# rad_detector_v500_PERIPHERAL.net
KiCad netlist of a schematic drawn in Altium Designer
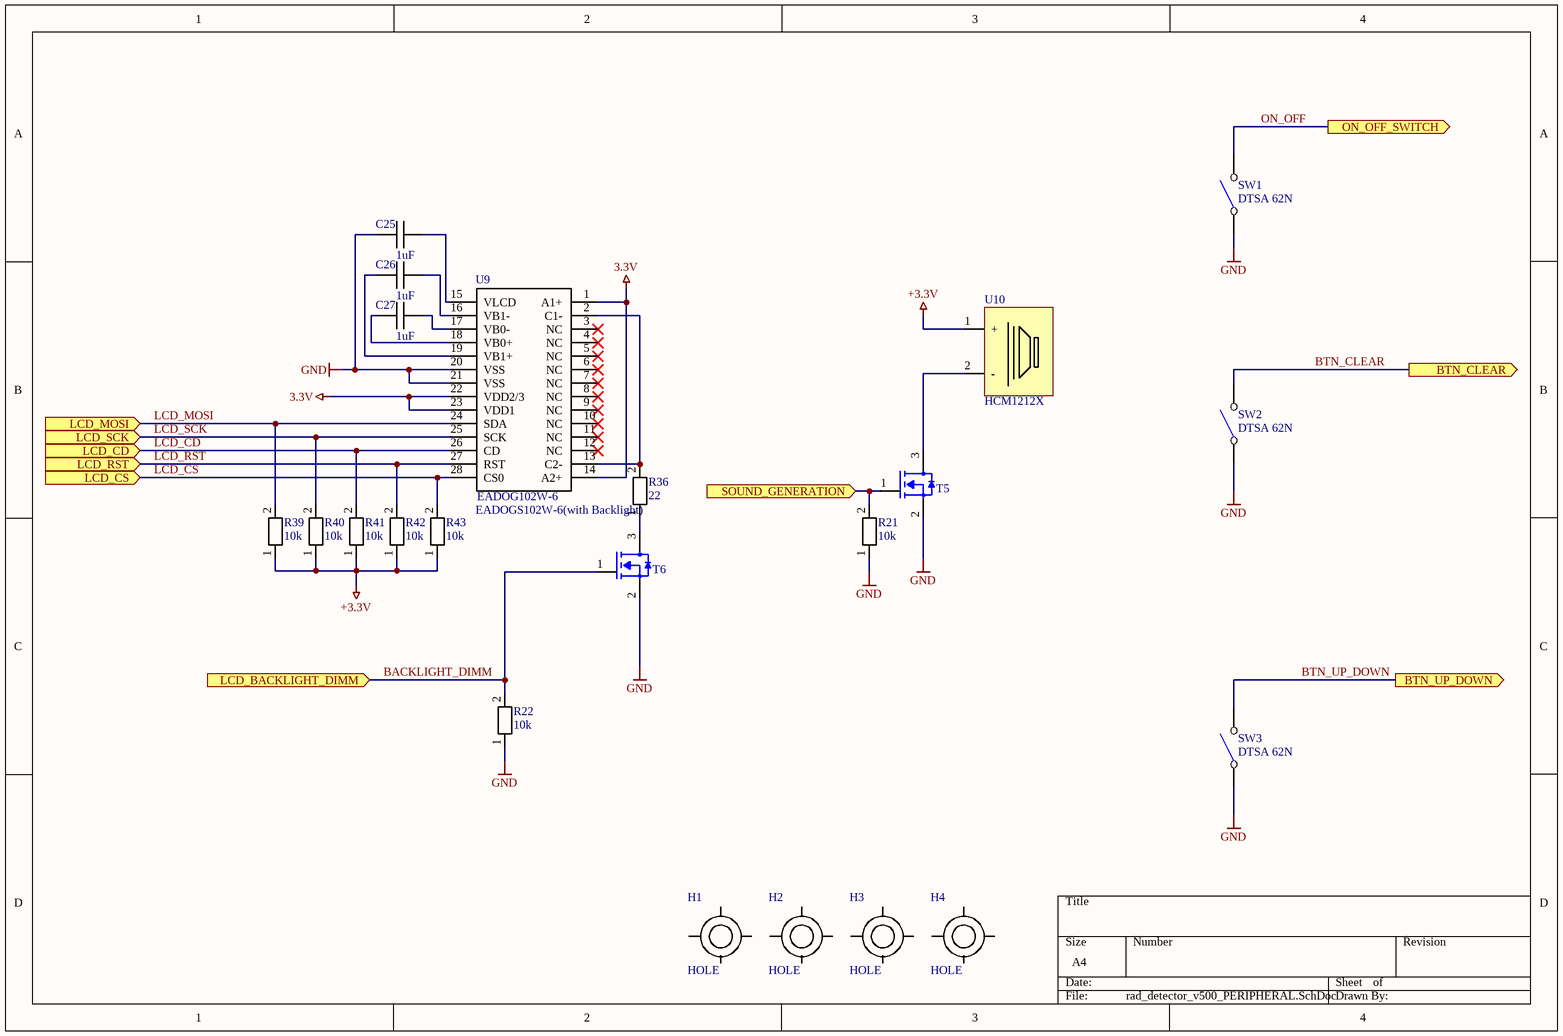
[diagram p0: rad_detector_v500_PERIPHERAL.SchDoc]

(export (version "E")
  (design (tool "Eeschema 10.0.6"))
  (components
    (comp (ref "C25") (value "1uF") (footprint "0805_C") (libsource (lib "Schlib1") (part "CAPACITOR")))
    (comp (ref "C26") (value "1uF") (footprint "0805_C") (libsource (lib "Schlib1") (part "CAPACITOR")))
    (comp (ref "C27") (value "1uF") (footprint "0805_C") (libsource (lib "Schlib1") (part "CAPACITOR")))
    (comp (ref "H1") (value "HOLE") (footprint "HOLE_140_160MIL") (libsource (lib "Schlib1") (part "HOLE")))
    (comp (ref "H2") (value "HOLE") (footprint "HOLE_140_160MIL") (libsource (lib "Schlib1") (part "HOLE")))
    (comp (ref "H3") (value "HOLE") (footprint "HOLE_140_160MIL") (libsource (lib "Schlib1") (part "HOLE")))
    (comp (ref "H4") (value "HOLE") (footprint "HOLE_140_160MIL") (libsource (lib "Schlib1") (part "HOLE")))
    (comp (ref "R21") (value "10k") (footprint "0805") (libsource (lib "Schlib1") (part "RESISTOR")))
    (comp (ref "R22") (value "10k") (footprint "0805") (libsource (lib "Schlib1") (part "RESISTOR")))
    (comp (ref "R36") (value "22") (footprint "1206") (libsource (lib "Schlib1") (part "RESISTOR")))
    (comp (ref "R39") (value "10k") (footprint "0805") (libsource (lib "Schlib1") (part "RESISTOR")))
    (comp (ref "R40") (value "10k") (footprint "0805") (libsource (lib "Schlib1") (part "RESISTOR")))
    (comp (ref "R41") (value "10k") (footprint "0805") (libsource (lib "Schlib1") (part "RESISTOR")))
    (comp (ref "R42") (value "10k") (footprint "0805") (libsource (lib "Schlib1") (part "RESISTOR")))
    (comp (ref "R43") (value "10k") (footprint "0805") (libsource (lib "Schlib1") (part "RESISTOR")))
    (comp (ref "SW1")
      (value "DTSA 62N")
      (footprint "SW_DTSA-62N")
      (libsource (lib "Schlib1") (part "SW_DTSA 62N"))
    )
    (comp (ref "SW2")
      (value "DTSA 62N")
      (footprint "SW_DTSA-62N")
      (libsource (lib "Schlib1") (part "SW_DTSA 62N"))
    )
    (comp (ref "SW3")
      (value "DTSA 62N")
      (footprint "SW_DTSA-62N")
      (libsource (lib "Schlib1") (part "SW_DTSA 62N"))
    )
    (comp (ref "T5")
      (value "MMBF170")
      (footprint "SOT23")
      (description "N MOSFET")
      (libsource (lib "Schlib1") (part "MMBF170"))
    )
    (comp (ref "T6")
      (value "MMBF170")
      (footprint "SOT23")
      (description "N MOSFET")
      (libsource (lib "Schlib1") (part "MMBF170"))
    )
    (comp (ref "U9")
      (value "EADOGS102W-6(with Backlight)")
      (footprint "EADOGS102-6W")
      (libsource (lib "ic_modules") (part "EADOGS102W-6(with Backlight)"))
    )
    (comp (ref "U10") (value "HCM1212X") (footprint "HCM1212X") (libsource (lib "Schlib1") (part "HCM1212X")))
  )
  (nets
    (net (code "1") (name "+3.3V") (class "Default")
      (node (ref "R39") (pin "1") (pinfunction "0_1") (pintype "passive"))
      (node (ref "R40") (pin "1") (pinfunction "0_1") (pintype "passive"))
      (node (ref "R41") (pin "1") (pinfunction "0_1") (pintype "passive"))
      (node (ref "R42") (pin "1") (pinfunction "0_1") (pintype "passive"))
      (node (ref "R43") (pin "1") (pinfunction "0_1") (pintype "passive"))
      (node (ref "U10") (pin "1") (pinfunction "+_1") (pintype "passive"))
    )
    (net (code "2") (name "/BACKLIGHT_DIMM") (class "Default")
      (node (ref "R22") (pin "2") (pinfunction "1_2") (pintype "passive"))
      (node (ref "T6") (pin "1") (pinfunction "Gate_1") (pintype "passive"))
    )
    (net (code "3") (name "/BTN_CLEAR") (class "Default")
      (node (ref "SW2") (pin "2") (pinfunction "2_2") (pintype "passive"))
    )
    (net (code "4") (name "/BTN_UP_DOWN") (class "Default")
      (node (ref "SW3") (pin "2") (pinfunction "2_2") (pintype "passive"))
    )
    (net (code "5") (name "/LCD_CD") (class "Default")
      (node (ref "R41") (pin "2") (pinfunction "1_2") (pintype "passive"))
      (node (ref "U9") (pin "26") (pinfunction "CD_26") (pintype "passive"))
    )
    (net (code "6") (name "/LCD_CS") (class "Default")
      (node (ref "R43") (pin "2") (pinfunction "1_2") (pintype "passive"))
      (node (ref "U9") (pin "28") (pinfunction "CS0_28") (pintype "passive"))
    )
    (net (code "7") (name "/LCD_MOSI") (class "Default")
      (node (ref "R39") (pin "2") (pinfunction "1_2") (pintype "passive"))
      (node (ref "U9") (pin "24") (pinfunction "SDA_24") (pintype "passive"))
    )
    (net (code "8") (name "/LCD_RST") (class "Default")
      (node (ref "R42") (pin "2") (pinfunction "1_2") (pintype "passive"))
      (node (ref "U9") (pin "27") (pinfunction "RST_27") (pintype "passive"))
    )
    (net (code "9") (name "/LCD_SCK") (class "Default")
      (node (ref "R40") (pin "2") (pinfunction "1_2") (pintype "passive"))
      (node (ref "U9") (pin "25") (pinfunction "SCK_25") (pintype "passive"))
    )
    (net (code "10") (name "/ON_OFF") (class "Default")
      (node (ref "SW1") (pin "2") (pinfunction "2_2") (pintype "passive"))
    )
    (net (code "11") (name "/SOUND_GENERATION") (class "Default")
      (node (ref "R21") (pin "2") (pinfunction "1_2") (pintype "passive"))
      (node (ref "T5") (pin "1") (pinfunction "Gate_1") (pintype "passive"))
    )
    (net (code "12") (name "3.3V") (class "Default")
      (node (ref "U9") (pin "1") (pinfunction "A1+_1") (pintype "passive"))
      (node (ref "U9") (pin "14") (pinfunction "A2+_14") (pintype "passive"))
      (node (ref "U9") (pin "22") (pinfunction "VDD2/3_22") (pintype "passive"))
      (node (ref "U9") (pin "23") (pinfunction "VDD1_23") (pintype "passive"))
    )
    (net (code "13") (name "GND") (class "Default")
      (node (ref "C25") (pin "1") (pinfunction "1_1") (pintype "passive"))
      (node (ref "R21") (pin "1") (pinfunction "0_1") (pintype "passive"))
      (node (ref "R22") (pin "1") (pinfunction "0_1") (pintype "passive"))
      (node (ref "SW1") (pin "1") (pinfunction "1_1") (pintype "passive"))
      (node (ref "SW2") (pin "1") (pinfunction "1_1") (pintype "passive"))
      (node (ref "SW3") (pin "1") (pinfunction "1_1") (pintype "passive"))
      (node (ref "T5") (pin "2") (pinfunction "Source_2") (pintype "passive"))
      (node (ref "T6") (pin "2") (pinfunction "Source_2") (pintype "passive"))
      (node (ref "U9") (pin "20") (pinfunction "VSS_20") (pintype "passive"))
      (node (ref "U9") (pin "21") (pinfunction "VSS_21") (pintype "passive"))
    )
    (net (code "14") (name "Net-(R36-0)") (class "Default")
      (node (ref "R36") (pin "1") (pinfunction "0_1") (pintype "passive"))
      (node (ref "T6") (pin "3") (pinfunction "Drain_3") (pintype "passive"))
    )
    (net (code "15") (name "Net-(R36-1)") (class "Default")
      (node (ref "R36") (pin "2") (pinfunction "1_2") (pintype "passive"))
      (node (ref "U9") (pin "13") (pinfunction "C2-_13") (pintype "passive"))
      (node (ref "U9") (pin "2") (pinfunction "C1-_2") (pintype "passive"))
    )
    (net (code "16") (name "Net-(T5-Drain)") (class "Default")
      (node (ref "T5") (pin "3") (pinfunction "Drain_3") (pintype "passive"))
      (node (ref "U10") (pin "2") (pinfunction "-_2") (pintype "passive"))
    )
    (net (code "17") (name "Net-(U9-VB0+)") (class "Default")
      (node (ref "C27") (pin "1") (pinfunction "1_1") (pintype "passive"))
      (node (ref "U9") (pin "18") (pinfunction "VB0+_18") (pintype "passive"))
    )
    (net (code "18") (name "Net-(U9-VB0-)") (class "Default")
      (node (ref "C27") (pin "2") (pinfunction "2_2") (pintype "passive"))
      (node (ref "U9") (pin "17") (pinfunction "VB0-_17") (pintype "passive"))
    )
    (net (code "19") (name "Net-(U9-VB1+)") (class "Default")
      (node (ref "C26") (pin "1") (pinfunction "1_1") (pintype "passive"))
      (node (ref "U9") (pin "19") (pinfunction "VB1+_19") (pintype "passive"))
    )
    (net (code "20") (name "Net-(U9-VB1-)") (class "Default")
      (node (ref "C26") (pin "2") (pinfunction "2_2") (pintype "passive"))
      (node (ref "U9") (pin "16") (pinfunction "VB1-_16") (pintype "passive"))
    )
    (net (code "21") (name "Net-(U9-VLCD)") (class "Default")
      (node (ref "C25") (pin "2") (pinfunction "2_2") (pintype "passive"))
      (node (ref "U9") (pin "15") (pinfunction "VLCD_15") (pintype "passive"))
    )
    (net (code "22") (name "unconnected-(U9-NC-Pad3)") (class "Default")
      (node (ref "U9") (pin "3") (pinfunction "NC_3") (pintype "passive+no_connect"))
    )
    (net (code "23") (name "unconnected-(U9-NC-Pad4)") (class "Default")
      (node (ref "U9") (pin "4") (pinfunction "NC_4") (pintype "passive+no_connect"))
    )
    (net (code "24") (name "unconnected-(U9-NC-Pad5)") (class "Default")
      (node (ref "U9") (pin "5") (pinfunction "NC_5") (pintype "passive+no_connect"))
    )
    (net (code "25") (name "unconnected-(U9-NC-Pad6)") (class "Default")
      (node (ref "U9") (pin "6") (pinfunction "NC_6") (pintype "passive+no_connect"))
    )
    (net (code "26") (name "unconnected-(U9-NC-Pad7)") (class "Default")
      (node (ref "U9") (pin "7") (pinfunction "NC_7") (pintype "passive+no_connect"))
    )
    (net (code "27") (name "unconnected-(U9-NC-Pad8)") (class "Default")
      (node (ref "U9") (pin "8") (pinfunction "NC_8") (pintype "passive+no_connect"))
    )
    (net (code "28") (name "unconnected-(U9-NC-Pad9)") (class "Default")
      (node (ref "U9") (pin "9") (pinfunction "NC_9") (pintype "passive+no_connect"))
    )
    (net (code "29") (name "unconnected-(U9-NC-Pad10)") (class "Default")
      (node (ref "U9") (pin "10") (pinfunction "NC_10") (pintype "passive+no_connect"))
    )
    (net (code "30") (name "unconnected-(U9-NC-Pad11)") (class "Default")
      (node (ref "U9") (pin "11") (pinfunction "NC_11") (pintype "passive+no_connect"))
    )
    (net (code "31") (name "unconnected-(U9-NC-Pad12)") (class "Default")
      (node (ref "U9") (pin "12") (pinfunction "NC_12") (pintype "passive+no_connect"))
    )
  )
)
